# Digital_board_schematic.net
KiCad netlist of a schematic drawn in Altium Designer
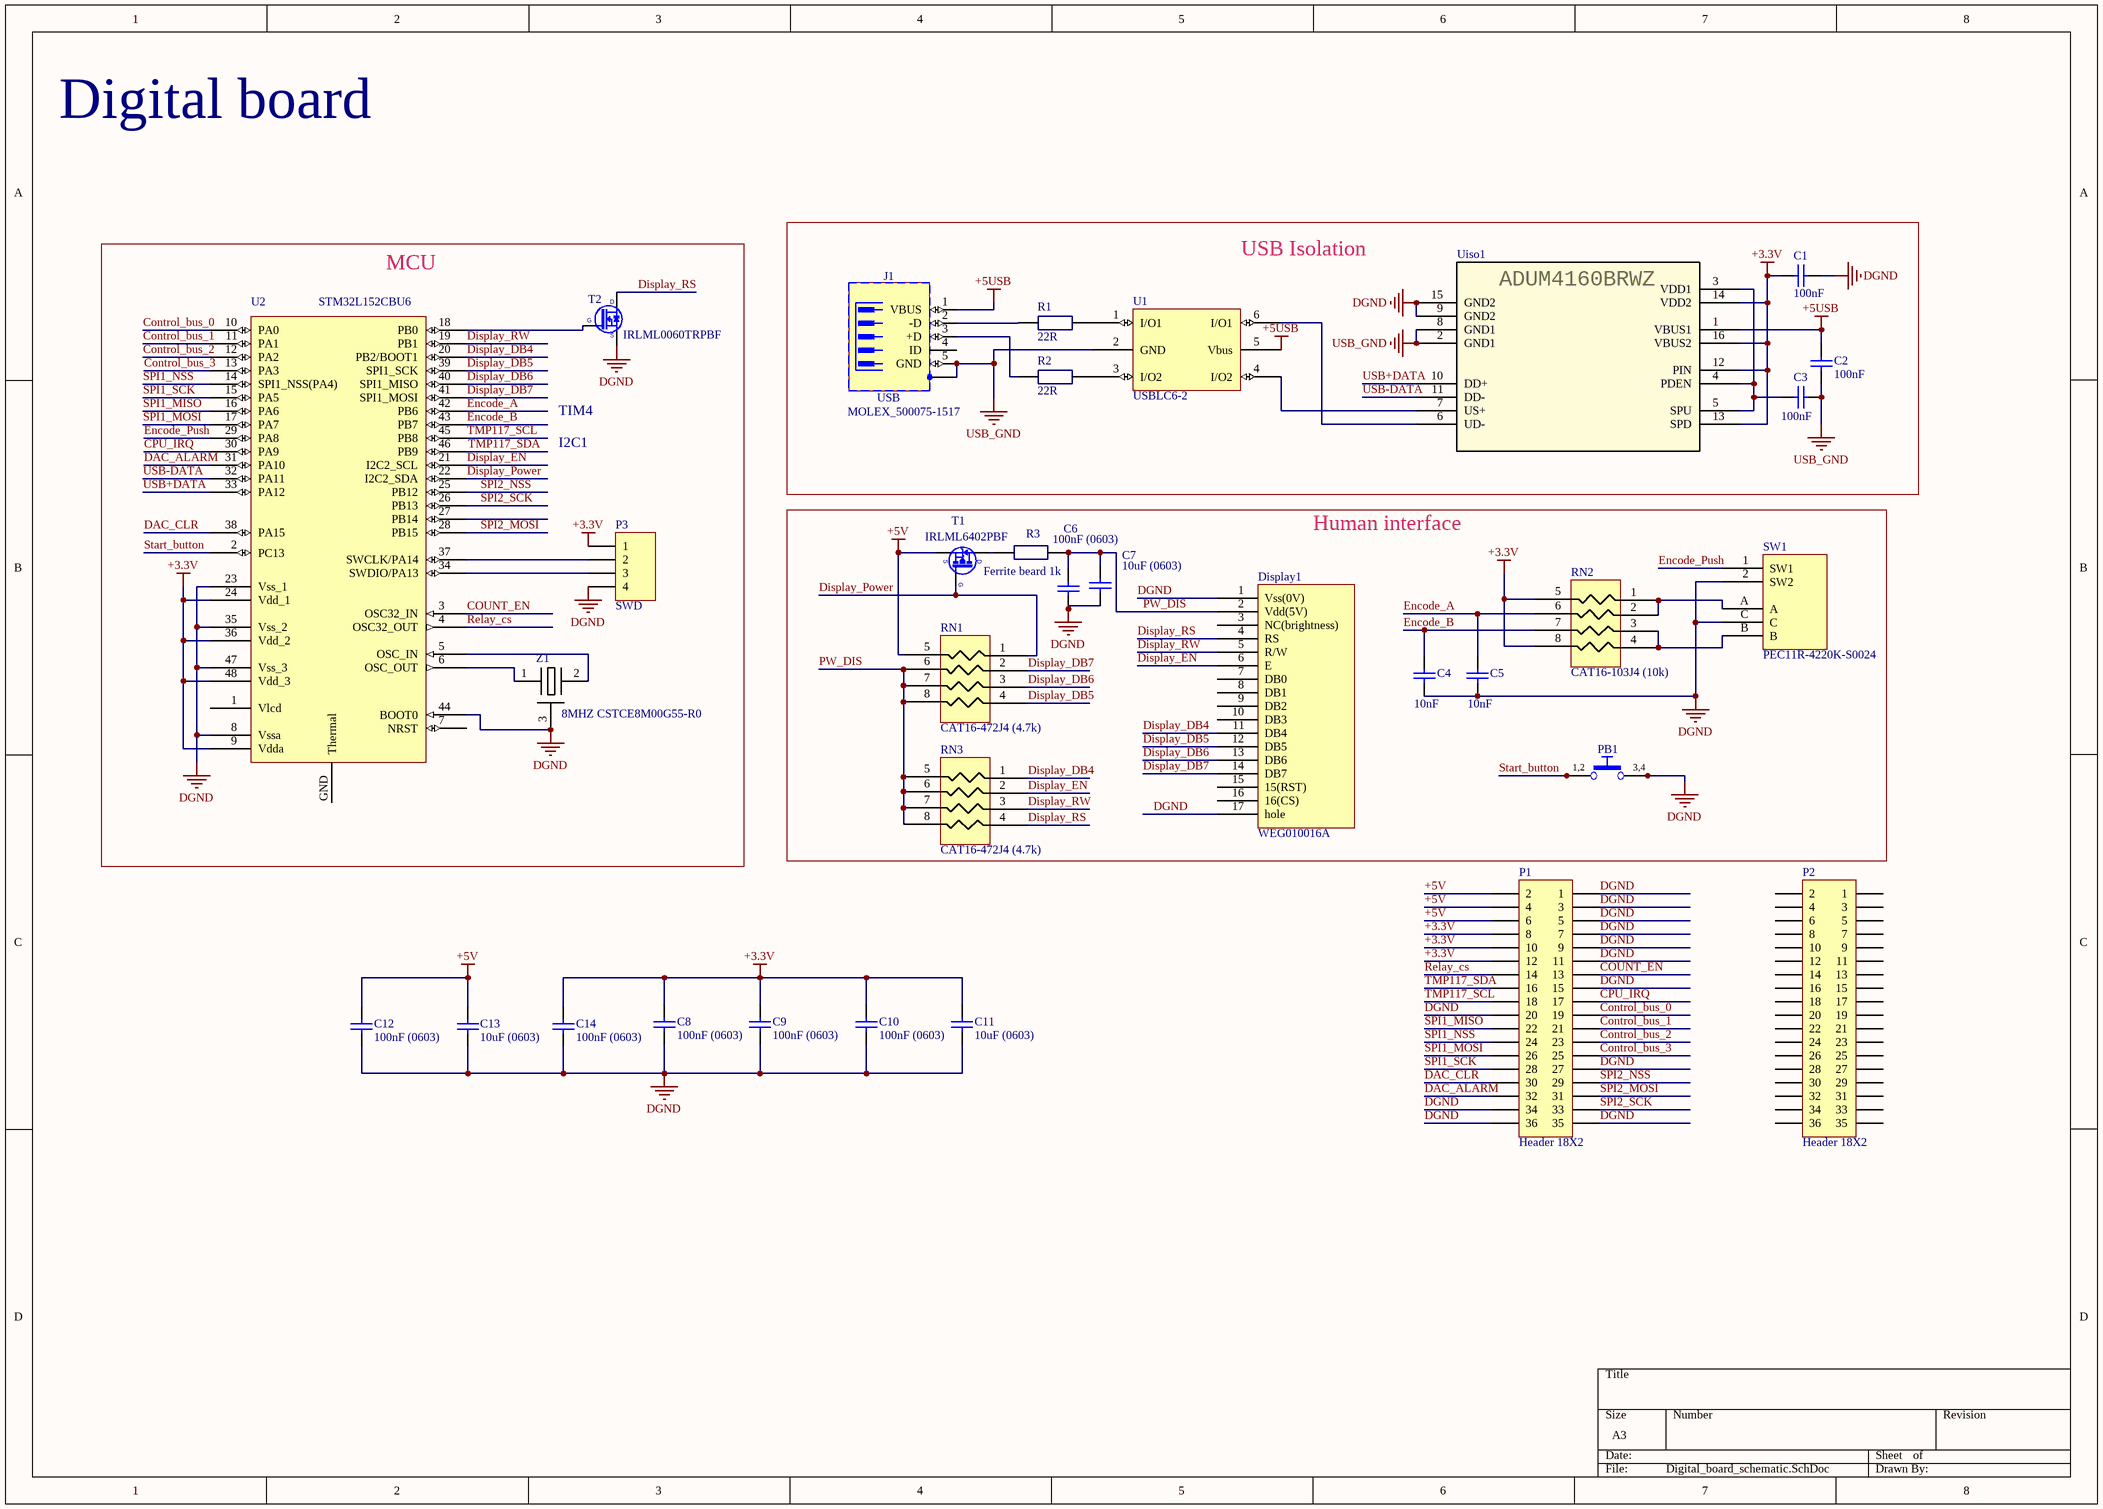
[diagram p0: Digital_board_schematic.SchDoc]

(export (version "E")
  (design (tool "Eeschema 10.0.6"))
  (components
    (comp (ref "C1")
      (value "100nF")
      (footprint "CAP 0603")
      (description "Capacitor (Semiconductor SIM Model)")
      (fields (field (name "PUBLISHER") "Altium Limited"))
      (libsource (lib "Miscellaneous Devices") (part "Cap Semi"))
    )
    (comp (ref "C2")
      (value "100nF")
      (footprint "CAP 0603")
      (description "Capacitor (Semiconductor SIM Model)")
      (fields (field (name "PUBLISHER") "Altium Limited"))
      (libsource (lib "Miscellaneous Devices") (part "Cap Semi"))
    )
    (comp (ref "C3")
      (value "100nF")
      (footprint "CAP 0603")
      (description "Capacitor (Semiconductor SIM Model)")
      (fields (field (name "PUBLISHER") "Altium Limited"))
      (libsource (lib "Miscellaneous Devices") (part "Cap Semi"))
    )
    (comp (ref "C4")
      (value "10nF")
      (footprint "CAP 0603")
      (description "Capacitor (Semiconductor SIM Model)")
      (fields (field (name "PUBLISHER") "Altium Limited"))
      (libsource (lib "Miscellaneous Devices") (part "Cap Semi"))
    )
    (comp (ref "C5")
      (value "10nF")
      (footprint "CAP 0603")
      (description "Capacitor (Semiconductor SIM Model)")
      (fields (field (name "PUBLISHER") "Altium Limited"))
      (libsource (lib "Miscellaneous Devices") (part "Cap Semi"))
    )
    (comp (ref "C6")
      (value "100nF (0603)")
      (footprint "CAP 0603")
      (description "Capacitor (Semiconductor SIM Model)")
      (fields (field (name "PUBLISHER") "Altium Limited"))
      (libsource (lib "Miscellaneous Devices") (part "Cap Semi"))
    )
    (comp (ref "C7")
      (value "10uF (0603)")
      (footprint "CAP 0603")
      (description "Capacitor (Semiconductor SIM Model)")
      (fields (field (name "PUBLISHER") "Altium Limited"))
      (libsource (lib "Miscellaneous Devices") (part "Cap Semi"))
    )
    (comp (ref "C8")
      (value "100nF (0603)")
      (footprint "CAP 0603")
      (description "Capacitor (Semiconductor SIM Model)")
      (fields (field (name "PUBLISHER") "Altium Limited"))
      (libsource (lib "Miscellaneous Devices") (part "Cap Semi"))
    )
    (comp (ref "C9")
      (value "100nF (0603)")
      (footprint "CAP 0603")
      (description "Capacitor (Semiconductor SIM Model)")
      (fields (field (name "PUBLISHER") "Altium Limited"))
      (libsource (lib "Miscellaneous Devices") (part "Cap Semi"))
    )
    (comp (ref "C10")
      (value "100nF (0603)")
      (footprint "CAP 0603")
      (description "Capacitor (Semiconductor SIM Model)")
      (fields (field (name "PUBLISHER") "Altium Limited"))
      (libsource (lib "Miscellaneous Devices") (part "Cap Semi"))
    )
    (comp (ref "C11")
      (value "10uF (0603)")
      (footprint "CAP 0603")
      (description "Capacitor (Semiconductor SIM Model)")
      (fields (field (name "PUBLISHER") "Altium Limited"))
      (libsource (lib "Miscellaneous Devices") (part "Cap Semi"))
    )
    (comp (ref "C12")
      (value "100nF (0603)")
      (footprint "CAP 0603")
      (description "Capacitor (Semiconductor SIM Model)")
      (fields (field (name "PUBLISHER") "Altium Limited"))
      (libsource (lib "Miscellaneous Devices") (part "Cap Semi"))
    )
    (comp (ref "C13")
      (value "10uF (0603)")
      (footprint "CAP 0603")
      (description "Capacitor (Semiconductor SIM Model)")
      (fields (field (name "PUBLISHER") "Altium Limited"))
      (libsource (lib "Miscellaneous Devices") (part "Cap Semi"))
    )
    (comp (ref "C14")
      (value "100nF (0603)")
      (footprint "CAP 0603")
      (description "Capacitor (Semiconductor SIM Model)")
      (fields (field (name "PUBLISHER") "Altium Limited"))
      (libsource (lib "Miscellaneous Devices") (part "Cap Semi"))
    )
    (comp (ref "Display1")
      (value "WEG010016A")
      (footprint "WEG010016A")
      (libsource (lib "My SCH library") (part "WEG010016A"))
    )
    (comp (ref "J1")
      (value "USB")
      (footprint "MOLEX_500075-1517")
      (description "5 Pin + 1 Shield USB Receptacle")
      (fields
        (field (name "PART NUMBER") "MOLEX_500075-1517")
        (field (name "MANUFACTURER") "MOLEX")
        (field (name "MANUFACTURER PART NUMBER") "500075-1517")
        (field (name "AUTHOR") "CERN DEM JLC")
      )
      (libsource (lib "Connectors") (part "Connector USB 5 Pin + 1Shield"))
    )
    (comp (ref "P1")
      (value "Header 18X2")
      (footprint "HDR2X18")
      (description "Header, 18-Pin, Dual row")
      (fields (field (name "PUBLISHER") "Altium Limited"))
      (libsource (lib "Miscellaneous Connectors") (part "Header 18X2"))
    )
    (comp (ref "P2")
      (value "Header 18X2")
      (footprint "HDR2X18")
      (description "Header, 18-Pin, Dual row")
      (fields (field (name "PUBLISHER") "Altium Limited"))
      (libsource (lib "Miscellaneous Connectors") (part "Header 18X2"))
    )
    (comp (ref "P3")
      (value "SWD")
      (footprint "HDR1X4")
      (description "Header, 4-Pin")
      (fields (field (name "PUBLISHER") "Altium Limited"))
      (libsource (lib "Miscellaneous Connectors") (part "Header 4"))
    )
    (comp (ref "PB1")
      (value "Push Button")
      (footprint "PB_OMRON_B3F-1070")
      (description "Push-Button Switch SPDT")
      (fields
        (field (name "PART NUMBER") "PB_OMRON_B3F-1070")
        (field (name "MANUFACTURER") "OMRON")
        (field (name "AUTHOR") "CERN DEM JLC")
      )
      (libsource (lib "Eletro-mechanical") (part "PB SPST 12NO-34NO"))
    )
    (comp (ref "R1")
      (value "22R")
      (footprint "1608[0603]")
      (libsource (lib "Микрон-3") (part "Resistor 0805"))
    )
    (comp (ref "R2")
      (value "22R")
      (footprint "1608[0603]")
      (libsource (lib "Микрон-3") (part "Resistor 0805"))
    )
    (comp (ref "R3")
      (value "Ferrite beard 1k")
      (footprint "C1206")
      (libsource (lib "Микрон-3") (part "Resistor 0805"))
    )
    (comp (ref "RN1")
      (value "CAT16-472J4 (4.7k)")
      (footprint "CAT16-470J4LF")
      (libsource (lib "My SCH library") (part "CAT16-470J4LF"))
    )
    (comp (ref "RN2")
      (value "CAT16-103J4 (10k)")
      (footprint "CAT16-470J4LF")
      (libsource (lib "My SCH library") (part "CAT16-470J4LF"))
    )
    (comp (ref "RN3")
      (value "CAT16-472J4 (4.7k)")
      (footprint "CAT16-470J4LF")
      (libsource (lib "My SCH library") (part "CAT16-470J4LF"))
    )
    (comp (ref "SW1")
      (value "PEC11R-4220K-S0024")
      (footprint "PEC11R-4220K-S0024")
      (libsource (lib "My SCH library") (part "PEC11R-4220K-S0024"))
    )
    (comp (ref "T1")
      (value "IRLML6402PBF")
      (footprint "SOT95P237X112-3N")
      (description "P-CHANNEL MOSFET WITH ZENER DIODE")
      (fields (field (name "MANUFACTURER") "INTERNATIONAL RECTIFIER") (field (name "AUTHOR") "CERN DEM JLC"))
      (libsource (lib "ICs And Semiconductors") (part "P-MOSFET-DZ 1G 2S 3D"))
    )
    (comp (ref "T2")
      (value "IRLML0060TRPBF")
      (footprint "SOT95P237X112-3N")
      (description "N-CHANNEL MOSFET WITH DIODE")
      (fields (field (name "MANUFACTURER") "INTERNATIONAL RECTIFIER") (field (name "AUTHOR") "CERN DEM JLC"))
      (libsource (lib "ICs And Semiconductors") (part "N-MOSFET-D 1G 2S 3D"))
    )
    (comp (ref "U1") (value "USBLC6-2") (footprint "SOT23-6L") (libsource (lib "Микрон-3") (part "USBLC6-2")))
    (comp (ref "U2")
      (value "STM32L152CBU6")
      (footprint "UFQFPN48")
      (libsource (lib "My SCH library") (part "STM32L152CBU6"))
    )
    (comp (ref "Uiso1")
      (value "~")
      (footprint "RW_16_ADI")
      (description "No Description Available")
      (fields
        (field (name "MANUFACTURER_PART_NUMBER") "ADUM4160BRWZ")
        (field (name "COPYRIGHT") "Copyright (C) 2018 Accelerated Designs. All rights reserved")
      )
      (libsource (lib "Ramp-generator") (part "ADUM4160BRWZ"))
    )
    (comp (ref "Z1")
      (value "8MHZ CSTCE8M00G55-R0")
      (footprint "PRQV8.00CR5010Y000")
      (libsource (lib "My SCH library") (part "8MHZ_cap"))
    )
  )
  (nets
    (net (code "1") (name "+3.3V") (class "Default")
      (node (ref "C1") (pin "2") (pinfunction "2_2") (pintype "passive"))
      (node (ref "C10") (pin "1") (pinfunction "1_1") (pintype "passive"))
      (node (ref "C11") (pin "1") (pinfunction "1_1") (pintype "passive"))
      (node (ref "C14") (pin "1") (pinfunction "1_1") (pintype "passive"))
      (node (ref "C8") (pin "1") (pinfunction "1_1") (pintype "passive"))
      (node (ref "C9") (pin "1") (pinfunction "1_1") (pintype "passive"))
      (node (ref "P1") (pin "10") (pinfunction "10_10") (pintype "passive"))
      (node (ref "P1") (pin "12") (pinfunction "12_12") (pintype "passive"))
      (node (ref "P1") (pin "8") (pinfunction "8_8") (pintype "passive"))
      (node (ref "P3") (pin "1") (pinfunction "1_1") (pintype "passive"))
      (node (ref "RN2") (pin "5") (pinfunction "5_5") (pintype "passive"))
      (node (ref "RN2") (pin "8") (pinfunction "8_8") (pintype "passive"))
      (node (ref "U2") (pin "24") (pinfunction "Vdd_1_24") (pintype "power_in"))
      (node (ref "U2") (pin "36") (pinfunction "Vdd_2_36") (pintype "power_in"))
      (node (ref "U2") (pin "48") (pinfunction "Vdd_3_48") (pintype "power_in"))
      (node (ref "U2") (pin "9") (pinfunction "Vdda_9") (pintype "power_in"))
      (node (ref "Uiso1") (pin "12") (pinfunction "PIN_12") (pintype "passive"))
      (node (ref "Uiso1") (pin "13") (pinfunction "SPD_13") (pintype "passive"))
      (node (ref "Uiso1") (pin "14") (pinfunction "VDD2_14") (pintype "passive"))
      (node (ref "Uiso1") (pin "16") (pinfunction "VBUS2_16") (pintype "passive"))
    )
    (net (code "2") (name "+5USB") (class "Default")
      (node (ref "C2") (pin "2") (pinfunction "2_2") (pintype "passive"))
      (node (ref "J1") (pin "1") (pinfunction "VBUS_1") (pintype "bidirectional"))
      (node (ref "U1") (pin "5") (pinfunction "Vbus_5") (pintype "power_in"))
      (node (ref "Uiso1") (pin "1") (pinfunction "VBUS1_1") (pintype "passive"))
    )
    (net (code "3") (name "+5V") (class "Default")
      (node (ref "C12") (pin "1") (pinfunction "1_1") (pintype "passive"))
      (node (ref "C13") (pin "1") (pinfunction "1_1") (pintype "passive"))
      (node (ref "P1") (pin "2") (pinfunction "2_2") (pintype "passive"))
      (node (ref "P1") (pin "4") (pinfunction "4_4") (pintype "passive"))
      (node (ref "P1") (pin "6") (pinfunction "6_6") (pintype "passive"))
      (node (ref "RN1") (pin "5") (pinfunction "5_5") (pintype "passive"))
      (node (ref "T1") (pin "2") (pinfunction "S_2") (pintype "passive"))
    )
    (net (code "4") (name "/COUNT_EN") (class "Default")
      (node (ref "P1") (pin "13") (pinfunction "13_13") (pintype "passive"))
      (node (ref "U2") (pin "3") (pinfunction "OSC32_IN_3") (pintype "input"))
    )
    (net (code "5") (name "/CPU_IRQ") (class "Default")
      (node (ref "P1") (pin "17") (pinfunction "17_17") (pintype "passive"))
      (node (ref "U2") (pin "30") (pinfunction "PA9_30") (pintype "bidirectional"))
    )
    (net (code "6") (name "/Control_bus_0") (class "Default")
      (node (ref "P1") (pin "19") (pinfunction "19_19") (pintype "passive"))
      (node (ref "U2") (pin "10") (pinfunction "PA0_10") (pintype "bidirectional"))
    )
    (net (code "7") (name "/Control_bus_1") (class "Default")
      (node (ref "P1") (pin "21") (pinfunction "21_21") (pintype "passive"))
      (node (ref "U2") (pin "11") (pinfunction "PA1_11") (pintype "bidirectional"))
    )
    (net (code "8") (name "/Control_bus_2") (class "Default")
      (node (ref "P1") (pin "23") (pinfunction "23_23") (pintype "passive"))
      (node (ref "U2") (pin "12") (pinfunction "PA2_12") (pintype "bidirectional"))
    )
    (net (code "9") (name "/Control_bus_3") (class "Default")
      (node (ref "P1") (pin "25") (pinfunction "25_25") (pintype "passive"))
      (node (ref "U2") (pin "13") (pinfunction "PA3_13") (pintype "bidirectional"))
    )
    (net (code "10") (name "/DAC_ALARM") (class "Default")
      (node (ref "P1") (pin "32") (pinfunction "32_32") (pintype "passive"))
      (node (ref "U2") (pin "31") (pinfunction "PA10_31") (pintype "bidirectional"))
    )
    (net (code "11") (name "/DAC_CLR") (class "Default")
      (node (ref "P1") (pin "30") (pinfunction "30_30") (pintype "passive"))
      (node (ref "U2") (pin "38") (pinfunction "PA15_38") (pintype "bidirectional"))
    )
    (net (code "12") (name "/Display_DB4") (class "Default")
      (node (ref "Display1") (pin "11") (pinfunction "DB4_11") (pintype "passive"))
      (node (ref "RN3") (pin "1") (pinfunction "1_1") (pintype "passive"))
      (node (ref "U2") (pin "20") (pinfunction "PB2/BOOT1_20") (pintype "bidirectional"))
    )
    (net (code "13") (name "/Display_DB5") (class "Default")
      (node (ref "Display1") (pin "12") (pinfunction "DB5_12") (pintype "passive"))
      (node (ref "RN1") (pin "4") (pinfunction "4_4") (pintype "passive"))
      (node (ref "U2") (pin "39") (pinfunction "SPI1_SCK_39") (pintype "bidirectional"))
    )
    (net (code "14") (name "/Display_DB6") (class "Default")
      (node (ref "Display1") (pin "13") (pinfunction "DB6_13") (pintype "passive"))
      (node (ref "RN1") (pin "3") (pinfunction "3_3") (pintype "passive"))
      (node (ref "U2") (pin "40") (pinfunction "SPI1_MISO_40") (pintype "bidirectional"))
    )
    (net (code "15") (name "/Display_DB7") (class "Default")
      (node (ref "Display1") (pin "14") (pinfunction "DB7_14") (pintype "passive"))
      (node (ref "RN1") (pin "2") (pinfunction "2_2") (pintype "passive"))
      (node (ref "U2") (pin "41") (pinfunction "SPI1_MOSI_41") (pintype "bidirectional"))
    )
    (net (code "16") (name "/Display_EN") (class "Default")
      (node (ref "Display1") (pin "6") (pinfunction "E_6") (pintype "passive"))
      (node (ref "RN3") (pin "2") (pinfunction "2_2") (pintype "passive"))
      (node (ref "U2") (pin "21") (pinfunction "I2C2_SCL_21") (pintype "bidirectional"))
    )
    (net (code "17") (name "/Display_Power") (class "Default")
      (node (ref "RN1") (pin "1") (pinfunction "1_1") (pintype "passive"))
      (node (ref "T1") (pin "1") (pinfunction "G_1") (pintype "passive"))
      (node (ref "U2") (pin "22") (pinfunction "I2C2_SDA_22") (pintype "bidirectional"))
    )
    (net (code "18") (name "/Display_RS") (class "Default")
      (node (ref "Display1") (pin "4") (pinfunction "RS_4") (pintype "passive"))
      (node (ref "RN3") (pin "4") (pinfunction "4_4") (pintype "passive"))
      (node (ref "T2") (pin "3") (pinfunction "D_3") (pintype "passive"))
    )
    (net (code "19") (name "/Display_RW") (class "Default")
      (node (ref "Display1") (pin "5") (pinfunction "R/W_5") (pintype "passive"))
      (node (ref "RN3") (pin "3") (pinfunction "3_3") (pintype "passive"))
      (node (ref "U2") (pin "19") (pinfunction "PB1_19") (pintype "bidirectional"))
    )
    (net (code "20") (name "/Encode_A") (class "Default")
      (node (ref "C5") (pin "1") (pinfunction "1_1") (pintype "passive"))
      (node (ref "RN2") (pin "6") (pinfunction "6_6") (pintype "passive"))
      (node (ref "U2") (pin "42") (pinfunction "PB6_42") (pintype "bidirectional"))
    )
    (net (code "21") (name "/Encode_B") (class "Default")
      (node (ref "C4") (pin "1") (pinfunction "1_1") (pintype "passive"))
      (node (ref "RN2") (pin "7") (pinfunction "7_7") (pintype "passive"))
      (node (ref "U2") (pin "43") (pinfunction "PB7_43") (pintype "bidirectional"))
    )
    (net (code "22") (name "/Encode_Push") (class "Default")
      (node (ref "SW1") (pin "1") (pinfunction "SW1_1") (pintype "open_collector"))
      (node (ref "U2") (pin "29") (pinfunction "PA8_29") (pintype "bidirectional"))
    )
    (net (code "23") (name "/PW_DIS") (class "Default")
      (node (ref "C6") (pin "1") (pinfunction "1_1") (pintype "passive"))
      (node (ref "C7") (pin "1") (pinfunction "1_1") (pintype "passive"))
      (node (ref "Display1") (pin "2") (pinfunction "Vdd(5V)_2") (pintype "passive"))
      (node (ref "R3") (pin "1") (pinfunction "A_1") (pintype "passive"))
      (node (ref "RN1") (pin "6") (pinfunction "6_6") (pintype "passive"))
      (node (ref "RN1") (pin "7") (pinfunction "7_7") (pintype "passive"))
      (node (ref "RN1") (pin "8") (pinfunction "8_8") (pintype "passive"))
      (node (ref "RN3") (pin "5") (pinfunction "5_5") (pintype "passive"))
      (node (ref "RN3") (pin "6") (pinfunction "6_6") (pintype "passive"))
      (node (ref "RN3") (pin "7") (pinfunction "7_7") (pintype "passive"))
      (node (ref "RN3") (pin "8") (pinfunction "8_8") (pintype "passive"))
    )
    (net (code "24") (name "/Relay_cs") (class "Default")
      (node (ref "P1") (pin "14") (pinfunction "14_14") (pintype "passive"))
      (node (ref "U2") (pin "4") (pinfunction "OSC32_OUT_4") (pintype "output"))
    )
    (net (code "25") (name "/SPI1_MISO") (class "Default")
      (node (ref "P1") (pin "22") (pinfunction "22_22") (pintype "passive"))
      (node (ref "U2") (pin "16") (pinfunction "PA6_16") (pintype "bidirectional"))
    )
    (net (code "26") (name "/SPI1_MOSI") (class "Default")
      (node (ref "P1") (pin "26") (pinfunction "26_26") (pintype "passive"))
      (node (ref "U2") (pin "17") (pinfunction "PA7_17") (pintype "bidirectional"))
    )
    (net (code "27") (name "/SPI1_NSS") (class "Default")
      (node (ref "P1") (pin "24") (pinfunction "24_24") (pintype "passive"))
      (node (ref "U2") (pin "14") (pinfunction "SPI1_NSS(PA4)_14") (pintype "bidirectional"))
    )
    (net (code "28") (name "/SPI1_SCK") (class "Default")
      (node (ref "P1") (pin "28") (pinfunction "28_28") (pintype "passive"))
      (node (ref "U2") (pin "15") (pinfunction "PA5_15") (pintype "bidirectional"))
    )
    (net (code "29") (name "/SPI2_MOSI") (class "Default")
      (node (ref "P1") (pin "31") (pinfunction "31_31") (pintype "passive"))
      (node (ref "U2") (pin "28") (pinfunction "PB15_28") (pintype "bidirectional"))
    )
    (net (code "30") (name "/SPI2_NSS") (class "Default")
      (node (ref "P1") (pin "29") (pinfunction "29_29") (pintype "passive"))
      (node (ref "U2") (pin "25") (pinfunction "PB12_25") (pintype "bidirectional"))
    )
    (net (code "31") (name "/SPI2_SCK") (class "Default")
      (node (ref "P1") (pin "33") (pinfunction "33_33") (pintype "passive"))
      (node (ref "U2") (pin "26") (pinfunction "PB13_26") (pintype "bidirectional"))
    )
    (net (code "32") (name "/Start_button") (class "Default")
      (node (ref "PB1") (pin "1") (pinfunction "1_1") (pintype "passive"))
      (node (ref "PB1") (pin "2") (pinfunction "2_2") (pintype "passive"))
      (node (ref "U2") (pin "2") (pinfunction "PC13_2") (pintype "bidirectional"))
    )
    (net (code "33") (name "/TMP117_SCL") (class "Default")
      (node (ref "P1") (pin "18") (pinfunction "18_18") (pintype "passive"))
      (node (ref "U2") (pin "45") (pinfunction "PB8_45") (pintype "bidirectional"))
    )
    (net (code "34") (name "/TMP117_SDA") (class "Default")
      (node (ref "P1") (pin "16") (pinfunction "16_16") (pintype "passive"))
      (node (ref "U2") (pin "46") (pinfunction "PB9_46") (pintype "bidirectional"))
    )
    (net (code "35") (name "/USB+DATA") (class "Default")
      (node (ref "U2") (pin "33") (pinfunction "PA12_33") (pintype "bidirectional"))
      (node (ref "Uiso1") (pin "10") (pinfunction "DD+_10") (pintype "passive"))
    )
    (net (code "36") (name "/USB-DATA") (class "Default")
      (node (ref "U2") (pin "32") (pinfunction "PA11_32") (pintype "bidirectional"))
      (node (ref "Uiso1") (pin "11") (pinfunction "DD-_11") (pintype "passive"))
    )
    (net (code "37") (name "DGND") (class "Default")
      (node (ref "C1") (pin "1") (pinfunction "1_1") (pintype "passive"))
      (node (ref "C10") (pin "2") (pinfunction "2_2") (pintype "passive"))
      (node (ref "C11") (pin "2") (pinfunction "2_2") (pintype "passive"))
      (node (ref "C12") (pin "2") (pinfunction "2_2") (pintype "passive"))
      (node (ref "C13") (pin "2") (pinfunction "2_2") (pintype "passive"))
      (node (ref "C14") (pin "2") (pinfunction "2_2") (pintype "passive"))
      (node (ref "C4") (pin "2") (pinfunction "2_2") (pintype "passive"))
      (node (ref "C5") (pin "2") (pinfunction "2_2") (pintype "passive"))
      (node (ref "C6") (pin "2") (pinfunction "2_2") (pintype "passive"))
      (node (ref "C7") (pin "2") (pinfunction "2_2") (pintype "passive"))
      (node (ref "C8") (pin "2") (pinfunction "2_2") (pintype "passive"))
      (node (ref "C9") (pin "2") (pinfunction "2_2") (pintype "passive"))
      (node (ref "Display1") (pin "1") (pinfunction "Vss(0V)_1") (pintype "passive"))
      (node (ref "Display1") (pin "17") (pinfunction "hole_17") (pintype "passive"))
      (node (ref "P1") (pin "1") (pinfunction "1_1") (pintype "passive"))
      (node (ref "P1") (pin "11") (pinfunction "11_11") (pintype "passive"))
      (node (ref "P1") (pin "15") (pinfunction "15_15") (pintype "passive"))
      (node (ref "P1") (pin "20") (pinfunction "20_20") (pintype "passive"))
      (node (ref "P1") (pin "27") (pinfunction "27_27") (pintype "passive"))
      (node (ref "P1") (pin "3") (pinfunction "3_3") (pintype "passive"))
      (node (ref "P1") (pin "34") (pinfunction "34_34") (pintype "passive"))
      (node (ref "P1") (pin "35") (pinfunction "35_35") (pintype "passive"))
      (node (ref "P1") (pin "36") (pinfunction "36_36") (pintype "passive"))
      (node (ref "P1") (pin "5") (pinfunction "5_5") (pintype "passive"))
      (node (ref "P1") (pin "7") (pinfunction "7_7") (pintype "passive"))
      (node (ref "P1") (pin "9") (pinfunction "9_9") (pintype "passive"))
      (node (ref "P3") (pin "4") (pinfunction "4_4") (pintype "passive"))
      (node (ref "PB1") (pin "3") (pinfunction "3_3") (pintype "passive"))
      (node (ref "PB1") (pin "4") (pinfunction "4_4") (pintype "passive"))
      (node (ref "SW1") (pin "2") (pinfunction "SW2_2") (pintype "open_collector"))
      (node (ref "SW1") (pin "C") (pinfunction "C_C") (pintype "open_collector"))
      (node (ref "T2") (pin "2") (pinfunction "S_2") (pintype "passive"))
      (node (ref "U2") (pin "23") (pinfunction "Vss_1_23") (pintype "power_in"))
      (node (ref "U2") (pin "35") (pinfunction "Vss_2_35") (pintype "power_in"))
      (node (ref "U2") (pin "44") (pinfunction "BOOT0_44") (pintype "input"))
      (node (ref "U2") (pin "47") (pinfunction "Vss_3_47") (pintype "power_in"))
      (node (ref "U2") (pin "8") (pinfunction "Vssa_8") (pintype "power_in"))
      (node (ref "Uiso1") (pin "15") (pinfunction "GND2_15") (pintype "passive"))
      (node (ref "Uiso1") (pin "9") (pinfunction "GND2_9") (pintype "passive"))
      (node (ref "Z1") (pin "3") (pinfunction "50_3") (pintype "passive"))
    )
    (net (code "38") (name "Net-(J1-+D)") (class "Default")
      (node (ref "J1") (pin "3") (pinfunction "+D_3") (pintype "bidirectional"))
      (node (ref "R2") (pin "2") (pinfunction "2_2") (pintype "passive"))
    )
    (net (code "39") (name "Net-(J1--D)") (class "Default")
      (node (ref "J1") (pin "2") (pinfunction "-D_2") (pintype "bidirectional"))
      (node (ref "R1") (pin "2") (pinfunction "2_2") (pintype "passive"))
    )
    (net (code "40") (name "Net-(R1-A)") (class "Default")
      (node (ref "R1") (pin "1") (pinfunction "A_1") (pintype "passive"))
      (node (ref "U1") (pin "1") (pinfunction "I/O1_1") (pintype "bidirectional"))
    )
    (net (code "41") (name "Net-(R2-A)") (class "Default")
      (node (ref "R2") (pin "1") (pinfunction "A_1") (pintype "passive"))
      (node (ref "U1") (pin "3") (pinfunction "I/O2_3") (pintype "bidirectional"))
    )
    (net (code "42") (name "Net-(RN2-Pad1)") (class "Default")
      (node (ref "RN2") (pin "1") (pinfunction "1_1") (pintype "passive"))
      (node (ref "RN2") (pin "2") (pinfunction "2_2") (pintype "passive"))
      (node (ref "SW1") (pin "A") (pinfunction "A_A") (pintype "open_collector"))
    )
    (net (code "43") (name "Net-(RN2-Pad3)") (class "Default")
      (node (ref "RN2") (pin "3") (pinfunction "3_3") (pintype "passive"))
      (node (ref "RN2") (pin "4") (pinfunction "4_4") (pintype "passive"))
      (node (ref "SW1") (pin "B") (pinfunction "B_B") (pintype "open_collector"))
    )
    (net (code "44") (name "Net-(T1-D)") (class "Default")
      (node (ref "R3") (pin "2") (pinfunction "2_2") (pintype "passive"))
      (node (ref "T1") (pin "3") (pinfunction "D_3") (pintype "passive"))
    )
    (net (code "45") (name "Net-(T2-G)") (class "Default")
      (node (ref "T2") (pin "1") (pinfunction "G_1") (pintype "passive"))
      (node (ref "U2") (pin "18") (pinfunction "PB0_18") (pintype "bidirectional"))
    )
    (net (code "46") (name "Net-(U2-OSC_IN)") (class "Default")
      (node (ref "U2") (pin "5") (pinfunction "OSC_IN_5") (pintype "input"))
      (node (ref "Z1") (pin "2") (pinfunction "2_2") (pintype "passive"))
    )
    (net (code "47") (name "Net-(U2-OSC_OUT)") (class "Default")
      (node (ref "U2") (pin "6") (pinfunction "OSC_OUT_6") (pintype "output"))
      (node (ref "Z1") (pin "1") (pinfunction "50_1") (pintype "passive"))
    )
    (net (code "48") (name "Net-(U2-SWCLK{slash}PA14)") (class "Default")
      (node (ref "P3") (pin "2") (pinfunction "2_2") (pintype "passive"))
      (node (ref "U2") (pin "37") (pinfunction "SWCLK/PA14_37") (pintype "bidirectional"))
    )
    (net (code "49") (name "Net-(U2-SWDIO{slash}PA13)") (class "Default")
      (node (ref "P3") (pin "3") (pinfunction "3_3") (pintype "passive"))
      (node (ref "U2") (pin "34") (pinfunction "SWDIO/PA13_34") (pintype "bidirectional"))
    )
    (net (code "50") (name "Net-(Uiso1-PDEN)") (class "Default")
      (node (ref "C3") (pin "2") (pinfunction "2_2") (pintype "passive"))
      (node (ref "Uiso1") (pin "3") (pinfunction "VDD1_3") (pintype "passive"))
      (node (ref "Uiso1") (pin "4") (pinfunction "PDEN_4") (pintype "passive"))
      (node (ref "Uiso1") (pin "5") (pinfunction "SPU_5") (pintype "passive"))
    )
    (net (code "51") (name "Net-(Uiso1-UD-)") (class "Default")
      (node (ref "U1") (pin "6") (pinfunction "I/O1_6") (pintype "bidirectional"))
      (node (ref "Uiso1") (pin "6") (pinfunction "UD-_6") (pintype "passive"))
    )
    (net (code "52") (name "Net-(Uiso1-US+)") (class "Default")
      (node (ref "U1") (pin "4") (pinfunction "I/O2_4") (pintype "bidirectional"))
      (node (ref "Uiso1") (pin "7") (pinfunction "US+_7") (pintype "passive"))
    )
    (net (code "53") (name "USB_GND") (class "Default")
      (node (ref "C2") (pin "1") (pinfunction "1_1") (pintype "passive"))
      (node (ref "C3") (pin "1") (pinfunction "1_1") (pintype "passive"))
      (node (ref "J1") (pin "5") (pinfunction "GND_5") (pintype "bidirectional"))
      (node (ref "J1") (pin "6") (pinfunction "SH_6") (pintype "power_in"))
      (node (ref "U1") (pin "2") (pinfunction "GND_2") (pintype "power_in"))
      (node (ref "Uiso1") (pin "2") (pinfunction "GND1_2") (pintype "passive"))
      (node (ref "Uiso1") (pin "8") (pinfunction "GND1_8") (pintype "passive"))
    )
    (net (code "54") (name "unconnected-(Display1-15(RST)-Pad15)") (class "Default")
      (node (ref "Display1") (pin "15") (pinfunction "15(RST)_15") (pintype "passive"))
    )
    (net (code "55") (name "unconnected-(Display1-16(CS)-Pad16)") (class "Default")
      (node (ref "Display1") (pin "16") (pinfunction "16(CS)_16") (pintype "passive"))
    )
    (net (code "56") (name "unconnected-(Display1-DB0-Pad7)") (class "Default")
      (node (ref "Display1") (pin "7") (pinfunction "DB0_7") (pintype "passive"))
    )
    (net (code "57") (name "unconnected-(Display1-DB1-Pad8)") (class "Default")
      (node (ref "Display1") (pin "8") (pinfunction "DB1_8") (pintype "passive"))
    )
    (net (code "58") (name "unconnected-(Display1-DB2-Pad9)") (class "Default")
      (node (ref "Display1") (pin "9") (pinfunction "DB2_9") (pintype "passive"))
    )
    (net (code "59") (name "unconnected-(Display1-DB3-Pad10)") (class "Default")
      (node (ref "Display1") (pin "10") (pinfunction "DB3_10") (pintype "passive"))
    )
    (net (code "60") (name "unconnected-(Display1-NC(brightness)-Pad3)") (class "Default")
      (node (ref "Display1") (pin "3") (pinfunction "NC(brightness)_3") (pintype "passive"))
    )
    (net (code "61") (name "unconnected-(J1-ID-Pad4)") (class "Default")
      (node (ref "J1") (pin "4") (pinfunction "ID_4") (pintype "passive"))
    )
    (net (code "62") (name "unconnected-(P2-Pad1)") (class "Default")
      (node (ref "P2") (pin "1") (pinfunction "1_1") (pintype "passive"))
    )
    (net (code "63") (name "unconnected-(P2-Pad2)") (class "Default")
      (node (ref "P2") (pin "2") (pinfunction "2_2") (pintype "passive"))
    )
    (net (code "64") (name "unconnected-(P2-Pad3)") (class "Default")
      (node (ref "P2") (pin "3") (pinfunction "3_3") (pintype "passive"))
    )
    (net (code "65") (name "unconnected-(P2-Pad4)") (class "Default")
      (node (ref "P2") (pin "4") (pinfunction "4_4") (pintype "passive"))
    )
    (net (code "66") (name "unconnected-(P2-Pad5)") (class "Default")
      (node (ref "P2") (pin "5") (pinfunction "5_5") (pintype "passive"))
    )
    (net (code "67") (name "unconnected-(P2-Pad6)") (class "Default")
      (node (ref "P2") (pin "6") (pinfunction "6_6") (pintype "passive"))
    )
    (net (code "68") (name "unconnected-(P2-Pad7)") (class "Default")
      (node (ref "P2") (pin "7") (pinfunction "7_7") (pintype "passive"))
    )
    (net (code "69") (name "unconnected-(P2-Pad8)") (class "Default")
      (node (ref "P2") (pin "8") (pinfunction "8_8") (pintype "passive"))
    )
    (net (code "70") (name "unconnected-(P2-Pad9)") (class "Default")
      (node (ref "P2") (pin "9") (pinfunction "9_9") (pintype "passive"))
    )
    (net (code "71") (name "unconnected-(P2-Pad10)") (class "Default")
      (node (ref "P2") (pin "10") (pinfunction "10_10") (pintype "passive"))
    )
    (net (code "72") (name "unconnected-(P2-Pad11)") (class "Default")
      (node (ref "P2") (pin "11") (pinfunction "11_11") (pintype "passive"))
    )
    (net (code "73") (name "unconnected-(P2-Pad12)") (class "Default")
      (node (ref "P2") (pin "12") (pinfunction "12_12") (pintype "passive"))
    )
    (net (code "74") (name "unconnected-(P2-Pad13)") (class "Default")
      (node (ref "P2") (pin "13") (pinfunction "13_13") (pintype "passive"))
    )
    (net (code "75") (name "unconnected-(P2-Pad14)") (class "Default")
      (node (ref "P2") (pin "14") (pinfunction "14_14") (pintype "passive"))
    )
    (net (code "76") (name "unconnected-(P2-Pad15)") (class "Default")
      (node (ref "P2") (pin "15") (pinfunction "15_15") (pintype "passive"))
    )
    (net (code "77") (name "unconnected-(P2-Pad16)") (class "Default")
      (node (ref "P2") (pin "16") (pinfunction "16_16") (pintype "passive"))
    )
    (net (code "78") (name "unconnected-(P2-Pad17)") (class "Default")
      (node (ref "P2") (pin "17") (pinfunction "17_17") (pintype "passive"))
    )
    (net (code "79") (name "unconnected-(P2-Pad18)") (class "Default")
      (node (ref "P2") (pin "18") (pinfunction "18_18") (pintype "passive"))
    )
    (net (code "80") (name "unconnected-(P2-Pad19)") (class "Default")
      (node (ref "P2") (pin "19") (pinfunction "19_19") (pintype "passive"))
    )
    (net (code "81") (name "unconnected-(P2-Pad20)") (class "Default")
      (node (ref "P2") (pin "20") (pinfunction "20_20") (pintype "passive"))
    )
    (net (code "82") (name "unconnected-(P2-Pad21)") (class "Default")
      (node (ref "P2") (pin "21") (pinfunction "21_21") (pintype "passive"))
    )
    (net (code "83") (name "unconnected-(P2-Pad22)") (class "Default")
      (node (ref "P2") (pin "22") (pinfunction "22_22") (pintype "passive"))
    )
    (net (code "84") (name "unconnected-(P2-Pad23)") (class "Default")
      (node (ref "P2") (pin "23") (pinfunction "23_23") (pintype "passive"))
    )
    (net (code "85") (name "unconnected-(P2-Pad24)") (class "Default")
      (node (ref "P2") (pin "24") (pinfunction "24_24") (pintype "passive"))
    )
    (net (code "86") (name "unconnected-(P2-Pad25)") (class "Default")
      (node (ref "P2") (pin "25") (pinfunction "25_25") (pintype "passive"))
    )
    (net (code "87") (name "unconnected-(P2-Pad26)") (class "Default")
      (node (ref "P2") (pin "26") (pinfunction "26_26") (pintype "passive"))
    )
    (net (code "88") (name "unconnected-(P2-Pad27)") (class "Default")
      (node (ref "P2") (pin "27") (pinfunction "27_27") (pintype "passive"))
    )
    (net (code "89") (name "unconnected-(P2-Pad28)") (class "Default")
      (node (ref "P2") (pin "28") (pinfunction "28_28") (pintype "passive"))
    )
    (net (code "90") (name "unconnected-(P2-Pad29)") (class "Default")
      (node (ref "P2") (pin "29") (pinfunction "29_29") (pintype "passive"))
    )
    (net (code "91") (name "unconnected-(P2-Pad30)") (class "Default")
      (node (ref "P2") (pin "30") (pinfunction "30_30") (pintype "passive"))
    )
    (net (code "92") (name "unconnected-(P2-Pad31)") (class "Default")
      (node (ref "P2") (pin "31") (pinfunction "31_31") (pintype "passive"))
    )
    (net (code "93") (name "unconnected-(P2-Pad32)") (class "Default")
      (node (ref "P2") (pin "32") (pinfunction "32_32") (pintype "passive"))
    )
    (net (code "94") (name "unconnected-(P2-Pad33)") (class "Default")
      (node (ref "P2") (pin "33") (pinfunction "33_33") (pintype "passive"))
    )
    (net (code "95") (name "unconnected-(P2-Pad34)") (class "Default")
      (node (ref "P2") (pin "34") (pinfunction "34_34") (pintype "passive"))
    )
    (net (code "96") (name "unconnected-(P2-Pad35)") (class "Default")
      (node (ref "P2") (pin "35") (pinfunction "35_35") (pintype "passive"))
    )
    (net (code "97") (name "unconnected-(P2-Pad36)") (class "Default")
      (node (ref "P2") (pin "36") (pinfunction "36_36") (pintype "passive"))
    )
    (net (code "98") (name "unconnected-(U2-NRST-Pad7)") (class "Default")
      (node (ref "U2") (pin "7") (pinfunction "NRST_7") (pintype "bidirectional"))
    )
    (net (code "99") (name "unconnected-(U2-PB14-Pad27)") (class "Default")
      (node (ref "U2") (pin "27") (pinfunction "PB14_27") (pintype "bidirectional"))
    )
    (net (code "100") (name "unconnected-(U2-Thermal-PadGND)") (class "Default")
      (node (ref "U2") (pin "GND") (pinfunction "Thermal_GND") (pintype "power_in"))
    )
    (net (code "101") (name "unconnected-(U2-Vlcd-Pad1)") (class "Default")
      (node (ref "U2") (pin "1") (pinfunction "Vlcd_1") (pintype "power_in"))
    )
  )
)
